# CR-10_Motherboard_2.net
KiCad netlist of a schematic drawn in Altium Designer
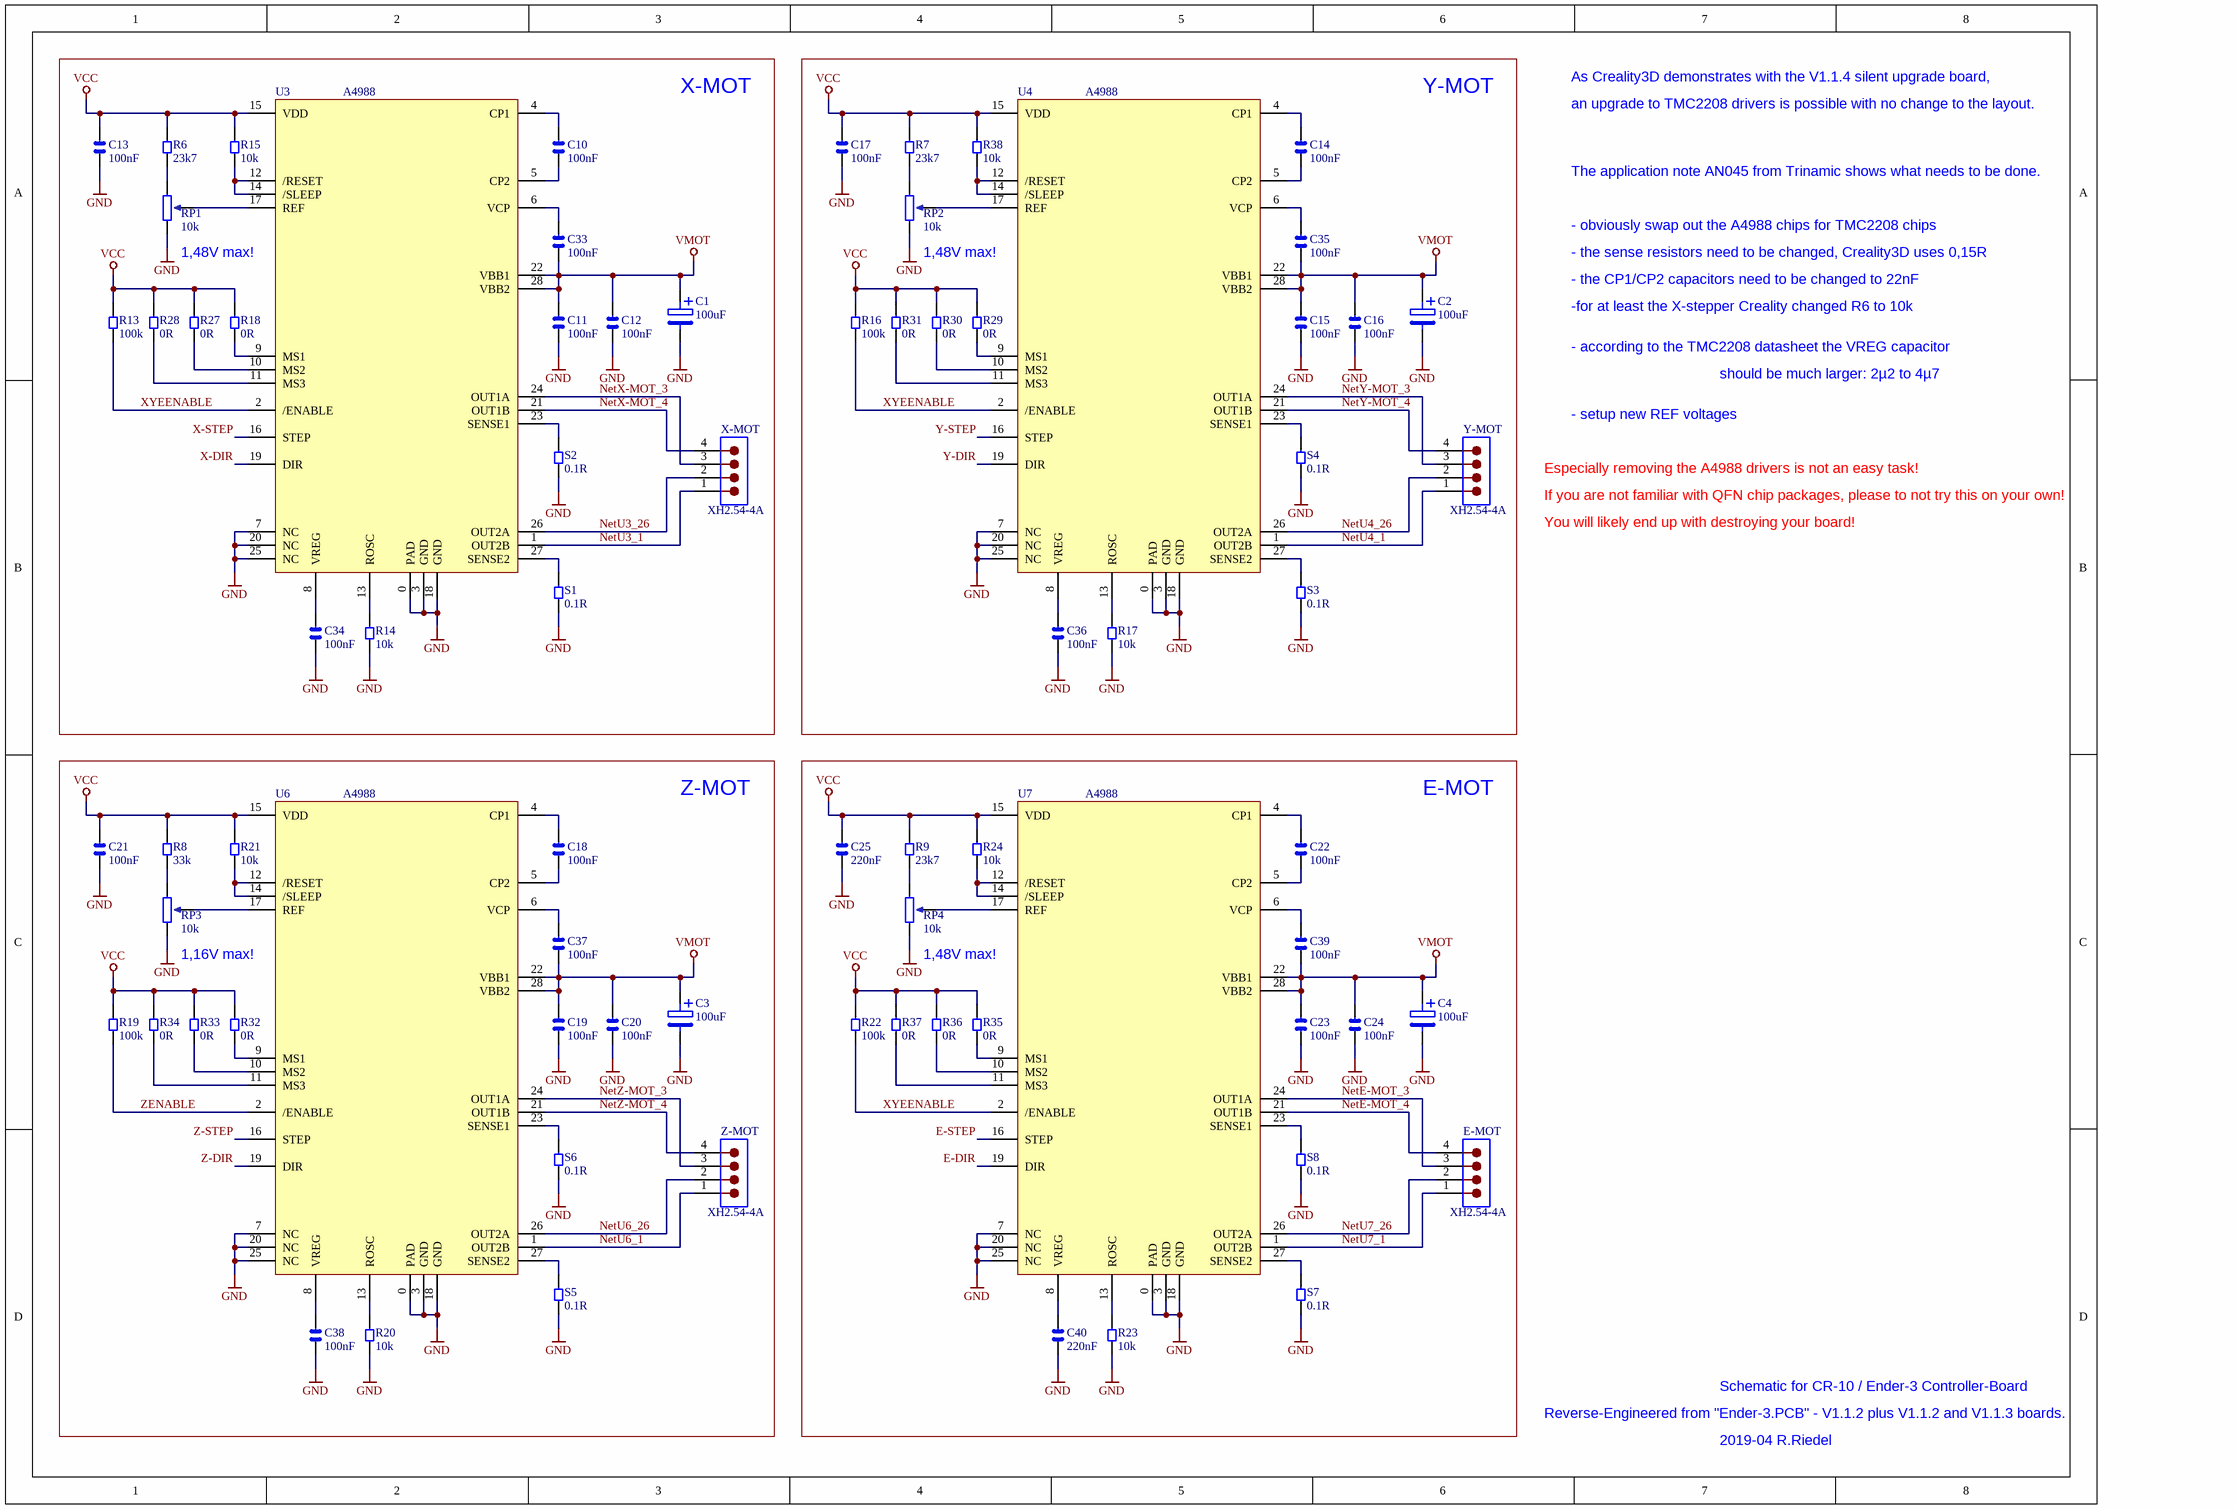
[diagram p0: CR-10 Motherboard_2.SchDoc]

(export (version "E")
  (design (tool "Eeschema 10.0.6"))
  (components
    (comp (ref "C1")
      (value "100uF")
      (footprint "Ender3:CAP-100")
      (description "Capacitor Polarized")
      (libsource (lib "CR-10 Motherboard") (part "Capacitor Pol"))
    )
    (comp (ref "C2")
      (value "100uF")
      (footprint "Ender3:CAP-100")
      (description "Capacitor Polarized")
      (libsource (lib "CR-10 Motherboard") (part "Capacitor Pol"))
    )
    (comp (ref "C3")
      (value "100uF")
      (footprint "Ender3:CAP-100")
      (description "Capacitor Polarized")
      (libsource (lib "CR-10 Motherboard") (part "Capacitor Pol"))
    )
    (comp (ref "C4")
      (value "100uF")
      (footprint "Ender3:CAP-100")
      (description "Capacitor Polarized")
      (libsource (lib "CR-10 Motherboard") (part "Capacitor Pol"))
    )
    (comp (ref "C10")
      (value "100nF")
      (footprint "Ender3:0603")
      (description "Chip Capacitor")
      (libsource (lib "CR-10 Motherboard") (part "Capacitor"))
    )
    (comp (ref "C11")
      (value "100nF")
      (footprint "Ender3:0603")
      (description "Chip Capacitor")
      (libsource (lib "CR-10 Motherboard") (part "Capacitor"))
    )
    (comp (ref "C12")
      (value "100nF")
      (footprint "Ender3:0603")
      (description "Chip Capacitor")
      (libsource (lib "CR-10 Motherboard") (part "Capacitor"))
    )
    (comp (ref "C13")
      (value "100nF")
      (footprint "Ender3:0603")
      (description "Chip Capacitor")
      (libsource (lib "CR-10 Motherboard") (part "Capacitor"))
    )
    (comp (ref "C14")
      (value "100nF")
      (footprint "Ender3:0603")
      (description "Chip Capacitor")
      (libsource (lib "CR-10 Motherboard") (part "Capacitor"))
    )
    (comp (ref "C15")
      (value "100nF")
      (footprint "Ender3:0603")
      (description "Chip Capacitor")
      (libsource (lib "CR-10 Motherboard") (part "Capacitor"))
    )
    (comp (ref "C16")
      (value "100nF")
      (footprint "Ender3:0603")
      (description "Chip Capacitor")
      (libsource (lib "CR-10 Motherboard") (part "Capacitor"))
    )
    (comp (ref "C17")
      (value "100nF")
      (footprint "Ender3:0603")
      (description "Chip Capacitor")
      (libsource (lib "CR-10 Motherboard") (part "Capacitor"))
    )
    (comp (ref "C18")
      (value "100nF")
      (footprint "Ender3:0603")
      (description "Chip Capacitor")
      (libsource (lib "CR-10 Motherboard") (part "Capacitor"))
    )
    (comp (ref "C19")
      (value "100nF")
      (footprint "Ender3:0603")
      (description "Chip Capacitor")
      (libsource (lib "CR-10 Motherboard") (part "Capacitor"))
    )
    (comp (ref "C20")
      (value "100nF")
      (footprint "Ender3:0603")
      (description "Chip Capacitor")
      (libsource (lib "CR-10 Motherboard") (part "Capacitor"))
    )
    (comp (ref "C21")
      (value "100nF")
      (footprint "Ender3:0603")
      (description "Chip Capacitor")
      (libsource (lib "CR-10 Motherboard") (part "Capacitor"))
    )
    (comp (ref "C22")
      (value "100nF")
      (footprint "Ender3:0603")
      (description "Chip Capacitor")
      (libsource (lib "CR-10 Motherboard") (part "Capacitor"))
    )
    (comp (ref "C23")
      (value "100nF")
      (footprint "Ender3:0603")
      (description "Chip Capacitor")
      (libsource (lib "CR-10 Motherboard") (part "Capacitor"))
    )
    (comp (ref "C24")
      (value "100nF")
      (footprint "Ender3:0603")
      (description "Chip Capacitor")
      (libsource (lib "CR-10 Motherboard") (part "Capacitor"))
    )
    (comp (ref "C25")
      (value "220nF")
      (footprint "Ender3:0603")
      (description "Chip Capacitor")
      (libsource (lib "CR-10 Motherboard") (part "Capacitor"))
    )
    (comp (ref "C33")
      (value "100nF")
      (footprint "Ender3:0603")
      (description "Chip Capacitor")
      (libsource (lib "CR-10 Motherboard") (part "Capacitor"))
    )
    (comp (ref "C34")
      (value "100nF")
      (footprint "Ender3:0603")
      (description "Chip Capacitor")
      (libsource (lib "CR-10 Motherboard") (part "Capacitor"))
    )
    (comp (ref "C35")
      (value "100nF")
      (footprint "Ender3:0603")
      (description "Chip Capacitor")
      (libsource (lib "CR-10 Motherboard") (part "Capacitor"))
    )
    (comp (ref "C36")
      (value "100nF")
      (footprint "Ender3:0603")
      (description "Chip Capacitor")
      (libsource (lib "CR-10 Motherboard") (part "Capacitor"))
    )
    (comp (ref "C37")
      (value "100nF")
      (footprint "Ender3:0603")
      (description "Chip Capacitor")
      (libsource (lib "CR-10 Motherboard") (part "Capacitor"))
    )
    (comp (ref "C38")
      (value "100nF")
      (footprint "Ender3:0603")
      (description "Chip Capacitor")
      (libsource (lib "CR-10 Motherboard") (part "Capacitor"))
    )
    (comp (ref "C39")
      (value "100nF")
      (footprint "Ender3:0603")
      (description "Chip Capacitor")
      (libsource (lib "CR-10 Motherboard") (part "Capacitor"))
    )
    (comp (ref "C40")
      (value "220nF")
      (footprint "Ender3:0603")
      (description "Chip Capacitor")
      (libsource (lib "CR-10 Motherboard") (part "Capacitor"))
    )
    (comp (ref "E-MOT")
      (value "XH2.54-4A")
      (footprint "Ender3:P4")
      (description "Header 1x4")
      (libsource (lib "CR-10 Motherboard") (part "Header 1x4"))
    )
    (comp (ref "R6")
      (value "23k7")
      (footprint "Ender3:0603")
      (description "Chip Resistor")
      (libsource (lib "CR-10 Motherboard") (part "Resistor"))
    )
    (comp (ref "R7")
      (value "23k7")
      (footprint "Ender3:0603")
      (description "Chip Resistor")
      (libsource (lib "CR-10 Motherboard") (part "Resistor"))
    )
    (comp (ref "R8")
      (value "33k")
      (footprint "Ender3:0603")
      (description "Chip Resistor")
      (libsource (lib "CR-10 Motherboard") (part "Resistor"))
    )
    (comp (ref "R9")
      (value "23k7")
      (footprint "Ender3:0603")
      (description "Chip Resistor")
      (libsource (lib "CR-10 Motherboard") (part "Resistor"))
    )
    (comp (ref "R13")
      (value "100k")
      (footprint "Ender3:0603")
      (description "Chip Resistor")
      (libsource (lib "CR-10 Motherboard") (part "Resistor"))
    )
    (comp (ref "R14")
      (value "10k")
      (footprint "Ender3:0603")
      (description "Chip Resistor")
      (libsource (lib "CR-10 Motherboard") (part "Resistor"))
    )
    (comp (ref "R15")
      (value "10k")
      (footprint "Ender3:0603")
      (description "Chip Resistor")
      (libsource (lib "CR-10 Motherboard") (part "Resistor"))
    )
    (comp (ref "R16")
      (value "100k")
      (footprint "Ender3:0603")
      (description "Chip Resistor")
      (libsource (lib "CR-10 Motherboard") (part "Resistor"))
    )
    (comp (ref "R17")
      (value "10k")
      (footprint "Ender3:0603")
      (description "Chip Resistor")
      (libsource (lib "CR-10 Motherboard") (part "Resistor"))
    )
    (comp (ref "R18")
      (value "0R")
      (footprint "Ender3:0603")
      (description "Chip Resistor")
      (libsource (lib "CR-10 Motherboard") (part "Resistor"))
    )
    (comp (ref "R19")
      (value "100k")
      (footprint "Ender3:0603")
      (description "Chip Resistor")
      (libsource (lib "CR-10 Motherboard") (part "Resistor"))
    )
    (comp (ref "R20")
      (value "10k")
      (footprint "Ender3:0603")
      (description "Chip Resistor")
      (libsource (lib "CR-10 Motherboard") (part "Resistor"))
    )
    (comp (ref "R21")
      (value "10k")
      (footprint "Ender3:0603")
      (description "Chip Resistor")
      (libsource (lib "CR-10 Motherboard") (part "Resistor"))
    )
    (comp (ref "R22")
      (value "100k")
      (footprint "Ender3:0603")
      (description "Chip Resistor")
      (libsource (lib "CR-10 Motherboard") (part "Resistor"))
    )
    (comp (ref "R23")
      (value "10k")
      (footprint "Ender3:0603")
      (description "Chip Resistor")
      (libsource (lib "CR-10 Motherboard") (part "Resistor"))
    )
    (comp (ref "R24")
      (value "10k")
      (footprint "Ender3:0603")
      (description "Chip Resistor")
      (libsource (lib "CR-10 Motherboard") (part "Resistor"))
    )
    (comp (ref "R27")
      (value "0R")
      (footprint "Ender3:0603")
      (description "Chip Resistor")
      (libsource (lib "CR-10 Motherboard") (part "Resistor"))
    )
    (comp (ref "R28")
      (value "0R")
      (footprint "Ender3:0603")
      (description "Chip Resistor")
      (libsource (lib "CR-10 Motherboard") (part "Resistor"))
    )
    (comp (ref "R29")
      (value "0R")
      (footprint "Ender3:0603")
      (description "Chip Resistor")
      (libsource (lib "CR-10 Motherboard") (part "Resistor"))
    )
    (comp (ref "R30")
      (value "0R")
      (footprint "Ender3:0603")
      (description "Chip Resistor")
      (libsource (lib "CR-10 Motherboard") (part "Resistor"))
    )
    (comp (ref "R31")
      (value "0R")
      (footprint "Ender3:0603")
      (description "Chip Resistor")
      (libsource (lib "CR-10 Motherboard") (part "Resistor"))
    )
    (comp (ref "R32")
      (value "0R")
      (footprint "Ender3:0603")
      (description "Chip Resistor")
      (libsource (lib "CR-10 Motherboard") (part "Resistor"))
    )
    (comp (ref "R33")
      (value "0R")
      (footprint "Ender3:0603")
      (description "Chip Resistor")
      (libsource (lib "CR-10 Motherboard") (part "Resistor"))
    )
    (comp (ref "R34")
      (value "0R")
      (footprint "Ender3:0603")
      (description "Chip Resistor")
      (libsource (lib "CR-10 Motherboard") (part "Resistor"))
    )
    (comp (ref "R35")
      (value "0R")
      (footprint "Ender3:0603")
      (description "Chip Resistor")
      (libsource (lib "CR-10 Motherboard") (part "Resistor"))
    )
    (comp (ref "R36")
      (value "0R")
      (footprint "Ender3:0603")
      (description "Chip Resistor")
      (libsource (lib "CR-10 Motherboard") (part "Resistor"))
    )
    (comp (ref "R37")
      (value "0R")
      (footprint "Ender3:0603")
      (description "Chip Resistor")
      (libsource (lib "CR-10 Motherboard") (part "Resistor"))
    )
    (comp (ref "R38")
      (value "10k")
      (footprint "Ender3:0603")
      (description "Chip Resistor")
      (libsource (lib "CR-10 Motherboard") (part "Resistor"))
    )
    (comp (ref "RP1")
      (value "10k")
      (footprint "Ender3:RP")
      (description "RTrimm")
      (libsource (lib "CR-10 Motherboard") (part "RTrimm"))
    )
    (comp (ref "RP2")
      (value "10k")
      (footprint "Ender3:RP")
      (description "RTrimm")
      (libsource (lib "CR-10 Motherboard") (part "RTrimm"))
    )
    (comp (ref "RP3")
      (value "10k")
      (footprint "Ender3:RP")
      (description "RTrimm")
      (libsource (lib "CR-10 Motherboard") (part "RTrimm"))
    )
    (comp (ref "RP4")
      (value "10k")
      (footprint "Ender3:RP")
      (description "RTrimm")
      (libsource (lib "CR-10 Motherboard") (part "RTrimm"))
    )
    (comp (ref "S1")
      (value "0.1R")
      (footprint "Ender3:R100")
      (description "Chip Resistor")
      (libsource (lib "CR-10 Motherboard") (part "Resistor"))
    )
    (comp (ref "S2")
      (value "0.1R")
      (footprint "Ender3:R100")
      (description "Chip Resistor")
      (libsource (lib "CR-10 Motherboard") (part "Resistor"))
    )
    (comp (ref "S3")
      (value "0.1R")
      (footprint "Ender3:R100")
      (description "Chip Resistor")
      (libsource (lib "CR-10 Motherboard") (part "Resistor"))
    )
    (comp (ref "S4")
      (value "0.1R")
      (footprint "Ender3:R100")
      (description "Chip Resistor")
      (libsource (lib "CR-10 Motherboard") (part "Resistor"))
    )
    (comp (ref "S5")
      (value "0.1R")
      (footprint "Ender3:R100")
      (description "Chip Resistor")
      (libsource (lib "CR-10 Motherboard") (part "Resistor"))
    )
    (comp (ref "S6")
      (value "0.1R")
      (footprint "Ender3:R100")
      (description "Chip Resistor")
      (libsource (lib "CR-10 Motherboard") (part "Resistor"))
    )
    (comp (ref "S7")
      (value "0.1R")
      (footprint "Ender3:R100")
      (description "Chip Resistor")
      (libsource (lib "CR-10 Motherboard") (part "Resistor"))
    )
    (comp (ref "S8")
      (value "0.1R")
      (footprint "Ender3:R100")
      (description "Chip Resistor")
      (libsource (lib "CR-10 Motherboard") (part "Resistor"))
    )
    (comp (ref "U3")
      (value "A4988")
      (footprint "Ender3:QFP28")
      (libsource (lib "CR-10 Motherboard") (part "A4988"))
    )
    (comp (ref "U4")
      (value "A4988")
      (footprint "Ender3:QFP28")
      (libsource (lib "CR-10 Motherboard") (part "A4988"))
    )
    (comp (ref "U6")
      (value "A4988")
      (footprint "Ender3:QFP28")
      (libsource (lib "CR-10 Motherboard") (part "A4988"))
    )
    (comp (ref "U7")
      (value "A4988")
      (footprint "Ender3:QFP28")
      (libsource (lib "CR-10 Motherboard") (part "A4988"))
    )
    (comp (ref "X-MOT")
      (value "XH2.54-4A")
      (footprint "Ender3:P4")
      (description "Header 1x4")
      (libsource (lib "CR-10 Motherboard") (part "Header 1x4"))
    )
    (comp (ref "Y-MOT")
      (value "XH2.54-4A")
      (footprint "Ender3:P4")
      (description "Header 1x4")
      (libsource (lib "CR-10 Motherboard") (part "Header 1x4"))
    )
    (comp (ref "Z-MOT")
      (value "XH2.54-4A")
      (footprint "Ender3:P4")
      (description "Header 1x4")
      (libsource (lib "CR-10 Motherboard") (part "Header 1x4"))
    )
  )
  (nets
    (net (code "1") (name "/E-DIR") (class "Default")
      (node (ref "U7") (pin "19") (pinfunction "DIR_19") (pintype "passive"))
    )
    (net (code "2") (name "/E-STEP") (class "Default")
      (node (ref "U7") (pin "16") (pinfunction "STEP_16") (pintype "passive"))
    )
    (net (code "3") (name "/NetE-MOT_3") (class "Default")
      (node (ref "E-MOT") (pin "3") (pinfunction "3_3") (pintype "passive"))
      (node (ref "U7") (pin "24") (pinfunction "OUT1A_24") (pintype "passive"))
    )
    (net (code "4") (name "/NetE-MOT_4") (class "Default")
      (node (ref "E-MOT") (pin "4") (pinfunction "4_4") (pintype "passive"))
      (node (ref "U7") (pin "21") (pinfunction "OUT1B_21") (pintype "passive"))
    )
    (net (code "5") (name "/NetU3_1") (class "Default")
      (node (ref "U3") (pin "1") (pinfunction "OUT2B_1") (pintype "passive"))
      (node (ref "X-MOT") (pin "1") (pinfunction "1_1") (pintype "passive"))
    )
    (net (code "6") (name "/NetU3_26") (class "Default")
      (node (ref "U3") (pin "26") (pinfunction "OUT2A_26") (pintype "passive"))
      (node (ref "X-MOT") (pin "2") (pinfunction "2_2") (pintype "passive"))
    )
    (net (code "7") (name "/NetU4_1") (class "Default")
      (node (ref "U4") (pin "1") (pinfunction "OUT2B_1") (pintype "passive"))
      (node (ref "Y-MOT") (pin "1") (pinfunction "1_1") (pintype "passive"))
    )
    (net (code "8") (name "/NetU4_26") (class "Default")
      (node (ref "U4") (pin "26") (pinfunction "OUT2A_26") (pintype "passive"))
      (node (ref "Y-MOT") (pin "2") (pinfunction "2_2") (pintype "passive"))
    )
    (net (code "9") (name "/NetU6_1") (class "Default")
      (node (ref "U6") (pin "1") (pinfunction "OUT2B_1") (pintype "passive"))
      (node (ref "Z-MOT") (pin "1") (pinfunction "1_1") (pintype "passive"))
    )
    (net (code "10") (name "/NetU6_26") (class "Default")
      (node (ref "U6") (pin "26") (pinfunction "OUT2A_26") (pintype "passive"))
      (node (ref "Z-MOT") (pin "2") (pinfunction "2_2") (pintype "passive"))
    )
    (net (code "11") (name "/NetU7_1") (class "Default")
      (node (ref "E-MOT") (pin "1") (pinfunction "1_1") (pintype "passive"))
      (node (ref "U7") (pin "1") (pinfunction "OUT2B_1") (pintype "passive"))
    )
    (net (code "12") (name "/NetU7_26") (class "Default")
      (node (ref "E-MOT") (pin "2") (pinfunction "2_2") (pintype "passive"))
      (node (ref "U7") (pin "26") (pinfunction "OUT2A_26") (pintype "passive"))
    )
    (net (code "13") (name "/NetX-MOT_3") (class "Default")
      (node (ref "U3") (pin "24") (pinfunction "OUT1A_24") (pintype "passive"))
      (node (ref "X-MOT") (pin "3") (pinfunction "3_3") (pintype "passive"))
    )
    (net (code "14") (name "/NetX-MOT_4") (class "Default")
      (node (ref "U3") (pin "21") (pinfunction "OUT1B_21") (pintype "passive"))
      (node (ref "X-MOT") (pin "4") (pinfunction "4_4") (pintype "passive"))
    )
    (net (code "15") (name "/NetY-MOT_3") (class "Default")
      (node (ref "U4") (pin "24") (pinfunction "OUT1A_24") (pintype "passive"))
      (node (ref "Y-MOT") (pin "3") (pinfunction "3_3") (pintype "passive"))
    )
    (net (code "16") (name "/NetY-MOT_4") (class "Default")
      (node (ref "U4") (pin "21") (pinfunction "OUT1B_21") (pintype "passive"))
      (node (ref "Y-MOT") (pin "4") (pinfunction "4_4") (pintype "passive"))
    )
    (net (code "17") (name "/NetZ-MOT_3") (class "Default")
      (node (ref "U6") (pin "24") (pinfunction "OUT1A_24") (pintype "passive"))
      (node (ref "Z-MOT") (pin "3") (pinfunction "3_3") (pintype "passive"))
    )
    (net (code "18") (name "/NetZ-MOT_4") (class "Default")
      (node (ref "U6") (pin "21") (pinfunction "OUT1B_21") (pintype "passive"))
      (node (ref "Z-MOT") (pin "4") (pinfunction "4_4") (pintype "passive"))
    )
    (net (code "19") (name "/X-DIR") (class "Default")
      (node (ref "U3") (pin "19") (pinfunction "DIR_19") (pintype "passive"))
    )
    (net (code "20") (name "/X-STEP") (class "Default")
      (node (ref "U3") (pin "16") (pinfunction "STEP_16") (pintype "passive"))
    )
    (net (code "21") (name "/XYEENABLE") (class "Default")
      (node (ref "R13") (pin "1") (pinfunction "1_1") (pintype "passive"))
      (node (ref "R16") (pin "1") (pinfunction "1_1") (pintype "passive"))
      (node (ref "R22") (pin "1") (pinfunction "1_1") (pintype "passive"))
      (node (ref "U3") (pin "2") (pinfunction "/ENABLE_2") (pintype "passive"))
      (node (ref "U4") (pin "2") (pinfunction "/ENABLE_2") (pintype "passive"))
      (node (ref "U7") (pin "2") (pinfunction "/ENABLE_2") (pintype "passive"))
    )
    (net (code "22") (name "/Y-DIR") (class "Default")
      (node (ref "U4") (pin "19") (pinfunction "DIR_19") (pintype "passive"))
    )
    (net (code "23") (name "/Y-STEP") (class "Default")
      (node (ref "U4") (pin "16") (pinfunction "STEP_16") (pintype "passive"))
    )
    (net (code "24") (name "/Z-DIR") (class "Default")
      (node (ref "U6") (pin "19") (pinfunction "DIR_19") (pintype "passive"))
    )
    (net (code "25") (name "/Z-STEP") (class "Default")
      (node (ref "U6") (pin "16") (pinfunction "STEP_16") (pintype "passive"))
    )
    (net (code "26") (name "/ZENABLE") (class "Default")
      (node (ref "R19") (pin "1") (pinfunction "1_1") (pintype "passive"))
      (node (ref "U6") (pin "2") (pinfunction "/ENABLE_2") (pintype "passive"))
    )
    (net (code "27") (name "GND") (class "Default")
      (node (ref "C1") (pin "2") (pinfunction "2_2") (pintype "passive"))
      (node (ref "C11") (pin "1") (pinfunction "1_1") (pintype "passive"))
      (node (ref "C12") (pin "2") (pinfunction "2_2") (pintype "passive"))
      (node (ref "C13") (pin "2") (pinfunction "2_2") (pintype "passive"))
      (node (ref "C15") (pin "1") (pinfunction "1_1") (pintype "passive"))
      (node (ref "C16") (pin "2") (pinfunction "2_2") (pintype "passive"))
      (node (ref "C17") (pin "2") (pinfunction "2_2") (pintype "passive"))
      (node (ref "C19") (pin "1") (pinfunction "1_1") (pintype "passive"))
      (node (ref "C2") (pin "2") (pinfunction "2_2") (pintype "passive"))
      (node (ref "C20") (pin "2") (pinfunction "2_2") (pintype "passive"))
      (node (ref "C21") (pin "2") (pinfunction "2_2") (pintype "passive"))
      (node (ref "C23") (pin "1") (pinfunction "1_1") (pintype "passive"))
      (node (ref "C24") (pin "2") (pinfunction "2_2") (pintype "passive"))
      (node (ref "C25") (pin "2") (pinfunction "2_2") (pintype "passive"))
      (node (ref "C3") (pin "2") (pinfunction "2_2") (pintype "passive"))
      (node (ref "C34") (pin "2") (pinfunction "2_2") (pintype "passive"))
      (node (ref "C36") (pin "2") (pinfunction "2_2") (pintype "passive"))
      (node (ref "C38") (pin "2") (pinfunction "2_2") (pintype "passive"))
      (node (ref "C4") (pin "2") (pinfunction "2_2") (pintype "passive"))
      (node (ref "C40") (pin "2") (pinfunction "2_2") (pintype "passive"))
      (node (ref "R14") (pin "2") (pinfunction "2_2") (pintype "passive"))
      (node (ref "R17") (pin "2") (pinfunction "2_2") (pintype "passive"))
      (node (ref "R20") (pin "2") (pinfunction "2_2") (pintype "passive"))
      (node (ref "R23") (pin "2") (pinfunction "2_2") (pintype "passive"))
      (node (ref "RP1") (pin "2") (pinfunction "2_2") (pintype "passive"))
      (node (ref "RP2") (pin "2") (pinfunction "2_2") (pintype "passive"))
      (node (ref "RP3") (pin "2") (pinfunction "2_2") (pintype "passive"))
      (node (ref "RP4") (pin "2") (pinfunction "2_2") (pintype "passive"))
      (node (ref "S1") (pin "2") (pinfunction "2_2") (pintype "passive"))
      (node (ref "S2") (pin "2") (pinfunction "2_2") (pintype "passive"))
      (node (ref "S3") (pin "2") (pinfunction "2_2") (pintype "passive"))
      (node (ref "S4") (pin "2") (pinfunction "2_2") (pintype "passive"))
      (node (ref "S5") (pin "2") (pinfunction "2_2") (pintype "passive"))
      (node (ref "S6") (pin "2") (pinfunction "2_2") (pintype "passive"))
      (node (ref "S7") (pin "2") (pinfunction "2_2") (pintype "passive"))
      (node (ref "S8") (pin "2") (pinfunction "2_2") (pintype "passive"))
      (node (ref "U3") (pin "0") (pinfunction "PAD_0") (pintype "passive"))
      (node (ref "U3") (pin "18") (pinfunction "GND_18") (pintype "passive"))
      (node (ref "U3") (pin "20") (pinfunction "NC_20") (pintype "passive"))
      (node (ref "U3") (pin "25") (pinfunction "NC_25") (pintype "passive"))
      (node (ref "U3") (pin "3") (pinfunction "GND_3") (pintype "passive"))
      (node (ref "U3") (pin "7") (pinfunction "NC_7") (pintype "passive"))
      (node (ref "U4") (pin "0") (pinfunction "PAD_0") (pintype "passive"))
      (node (ref "U4") (pin "18") (pinfunction "GND_18") (pintype "passive"))
      (node (ref "U4") (pin "20") (pinfunction "NC_20") (pintype "passive"))
      (node (ref "U4") (pin "25") (pinfunction "NC_25") (pintype "passive"))
      (node (ref "U4") (pin "3") (pinfunction "GND_3") (pintype "passive"))
      (node (ref "U4") (pin "7") (pinfunction "NC_7") (pintype "passive"))
      (node (ref "U6") (pin "0") (pinfunction "PAD_0") (pintype "passive"))
      (node (ref "U6") (pin "18") (pinfunction "GND_18") (pintype "passive"))
      (node (ref "U6") (pin "20") (pinfunction "NC_20") (pintype "passive"))
      (node (ref "U6") (pin "25") (pinfunction "NC_25") (pintype "passive"))
      (node (ref "U6") (pin "3") (pinfunction "GND_3") (pintype "passive"))
      (node (ref "U6") (pin "7") (pinfunction "NC_7") (pintype "passive"))
      (node (ref "U7") (pin "0") (pinfunction "PAD_0") (pintype "passive"))
      (node (ref "U7") (pin "18") (pinfunction "GND_18") (pintype "passive"))
      (node (ref "U7") (pin "20") (pinfunction "NC_20") (pintype "passive"))
      (node (ref "U7") (pin "25") (pinfunction "NC_25") (pintype "passive"))
      (node (ref "U7") (pin "3") (pinfunction "GND_3") (pintype "passive"))
      (node (ref "U7") (pin "7") (pinfunction "NC_7") (pintype "passive"))
    )
    (net (code "28") (name "Net-(R6-Pad1)") (class "Default")
      (node (ref "R6") (pin "1") (pinfunction "1_1") (pintype "passive"))
      (node (ref "RP1") (pin "3") (pinfunction "3_3") (pintype "passive"))
    )
    (net (code "29") (name "Net-(R7-Pad1)") (class "Default")
      (node (ref "R7") (pin "1") (pinfunction "1_1") (pintype "passive"))
      (node (ref "RP2") (pin "3") (pinfunction "3_3") (pintype "passive"))
    )
    (net (code "30") (name "Net-(R8-Pad1)") (class "Default")
      (node (ref "R8") (pin "1") (pinfunction "1_1") (pintype "passive"))
      (node (ref "RP3") (pin "3") (pinfunction "3_3") (pintype "passive"))
    )
    (net (code "31") (name "Net-(R9-Pad1)") (class "Default")
      (node (ref "R9") (pin "1") (pinfunction "1_1") (pintype "passive"))
      (node (ref "RP4") (pin "3") (pinfunction "3_3") (pintype "passive"))
    )
    (net (code "32") (name "Net-(U3-CP1)") (class "Default")
      (node (ref "C10") (pin "1") (pinfunction "1_1") (pintype "passive"))
      (node (ref "U3") (pin "4") (pinfunction "CP1_4") (pintype "passive"))
    )
    (net (code "33") (name "Net-(U3-CP2)") (class "Default")
      (node (ref "C10") (pin "2") (pinfunction "2_2") (pintype "passive"))
      (node (ref "U3") (pin "5") (pinfunction "CP2_5") (pintype "passive"))
    )
    (net (code "34") (name "Net-(U3-MS1)") (class "Default")
      (node (ref "R18") (pin "1") (pinfunction "1_1") (pintype "passive"))
      (node (ref "U3") (pin "9") (pinfunction "MS1_9") (pintype "passive"))
    )
    (net (code "35") (name "Net-(U3-MS2)") (class "Default")
      (node (ref "R27") (pin "1") (pinfunction "1_1") (pintype "passive"))
      (node (ref "U3") (pin "10") (pinfunction "MS2_10") (pintype "passive"))
    )
    (net (code "36") (name "Net-(U3-MS3)") (class "Default")
      (node (ref "R28") (pin "1") (pinfunction "1_1") (pintype "passive"))
      (node (ref "U3") (pin "11") (pinfunction "MS3_11") (pintype "passive"))
    )
    (net (code "37") (name "Net-(U3-REF)") (class "Default")
      (node (ref "RP1") (pin "1") (pinfunction "1_1") (pintype "passive"))
      (node (ref "U3") (pin "17") (pinfunction "REF_17") (pintype "passive"))
    )
    (net (code "38") (name "Net-(U3-ROSC)") (class "Default")
      (node (ref "R14") (pin "1") (pinfunction "1_1") (pintype "passive"))
      (node (ref "U3") (pin "13") (pinfunction "ROSC_13") (pintype "passive"))
    )
    (net (code "39") (name "Net-(U3-SENSE1)") (class "Default")
      (node (ref "S2") (pin "1") (pinfunction "1_1") (pintype "passive"))
      (node (ref "U3") (pin "23") (pinfunction "SENSE1_23") (pintype "passive"))
    )
    (net (code "40") (name "Net-(U3-SENSE2)") (class "Default")
      (node (ref "S1") (pin "1") (pinfunction "1_1") (pintype "passive"))
      (node (ref "U3") (pin "27") (pinfunction "SENSE2_27") (pintype "passive"))
    )
    (net (code "41") (name "Net-(U3-VCP)") (class "Default")
      (node (ref "C33") (pin "1") (pinfunction "1_1") (pintype "passive"))
      (node (ref "U3") (pin "6") (pinfunction "VCP_6") (pintype "passive"))
    )
    (net (code "42") (name "Net-(U3-VREG)") (class "Default")
      (node (ref "C34") (pin "1") (pinfunction "1_1") (pintype "passive"))
      (node (ref "U3") (pin "8") (pinfunction "VREG_8") (pintype "passive"))
    )
    (net (code "43") (name "Net-(U3-{slash}RESET)") (class "Default")
      (node (ref "R15") (pin "1") (pinfunction "1_1") (pintype "passive"))
      (node (ref "U3") (pin "12") (pinfunction "/RESET_12") (pintype "passive"))
      (node (ref "U3") (pin "14") (pinfunction "/SLEEP_14") (pintype "passive"))
    )
    (net (code "44") (name "Net-(U4-CP1)") (class "Default")
      (node (ref "C14") (pin "1") (pinfunction "1_1") (pintype "passive"))
      (node (ref "U4") (pin "4") (pinfunction "CP1_4") (pintype "passive"))
    )
    (net (code "45") (name "Net-(U4-CP2)") (class "Default")
      (node (ref "C14") (pin "2") (pinfunction "2_2") (pintype "passive"))
      (node (ref "U4") (pin "5") (pinfunction "CP2_5") (pintype "passive"))
    )
    (net (code "46") (name "Net-(U4-MS1)") (class "Default")
      (node (ref "R29") (pin "1") (pinfunction "1_1") (pintype "passive"))
      (node (ref "U4") (pin "9") (pinfunction "MS1_9") (pintype "passive"))
    )
    (net (code "47") (name "Net-(U4-MS2)") (class "Default")
      (node (ref "R30") (pin "1") (pinfunction "1_1") (pintype "passive"))
      (node (ref "U4") (pin "10") (pinfunction "MS2_10") (pintype "passive"))
    )
    (net (code "48") (name "Net-(U4-MS3)") (class "Default")
      (node (ref "R31") (pin "1") (pinfunction "1_1") (pintype "passive"))
      (node (ref "U4") (pin "11") (pinfunction "MS3_11") (pintype "passive"))
    )
    (net (code "49") (name "Net-(U4-REF)") (class "Default")
      (node (ref "RP2") (pin "1") (pinfunction "1_1") (pintype "passive"))
      (node (ref "U4") (pin "17") (pinfunction "REF_17") (pintype "passive"))
    )
    (net (code "50") (name "Net-(U4-ROSC)") (class "Default")
      (node (ref "R17") (pin "1") (pinfunction "1_1") (pintype "passive"))
      (node (ref "U4") (pin "13") (pinfunction "ROSC_13") (pintype "passive"))
    )
    (net (code "51") (name "Net-(U4-SENSE1)") (class "Default")
      (node (ref "S4") (pin "1") (pinfunction "1_1") (pintype "passive"))
      (node (ref "U4") (pin "23") (pinfunction "SENSE1_23") (pintype "passive"))
    )
    (net (code "52") (name "Net-(U4-SENSE2)") (class "Default")
      (node (ref "S3") (pin "1") (pinfunction "1_1") (pintype "passive"))
      (node (ref "U4") (pin "27") (pinfunction "SENSE2_27") (pintype "passive"))
    )
    (net (code "53") (name "Net-(U4-VCP)") (class "Default")
      (node (ref "C35") (pin "1") (pinfunction "1_1") (pintype "passive"))
      (node (ref "U4") (pin "6") (pinfunction "VCP_6") (pintype "passive"))
    )
    (net (code "54") (name "Net-(U4-VREG)") (class "Default")
      (node (ref "C36") (pin "1") (pinfunction "1_1") (pintype "passive"))
      (node (ref "U4") (pin "8") (pinfunction "VREG_8") (pintype "passive"))
    )
    (net (code "55") (name "Net-(U4-{slash}RESET)") (class "Default")
      (node (ref "R38") (pin "1") (pinfunction "1_1") (pintype "passive"))
      (node (ref "U4") (pin "12") (pinfunction "/RESET_12") (pintype "passive"))
      (node (ref "U4") (pin "14") (pinfunction "/SLEEP_14") (pintype "passive"))
    )
    (net (code "56") (name "Net-(U6-CP1)") (class "Default")
      (node (ref "C18") (pin "1") (pinfunction "1_1") (pintype "passive"))
      (node (ref "U6") (pin "4") (pinfunction "CP1_4") (pintype "passive"))
    )
    (net (code "57") (name "Net-(U6-CP2)") (class "Default")
      (node (ref "C18") (pin "2") (pinfunction "2_2") (pintype "passive"))
      (node (ref "U6") (pin "5") (pinfunction "CP2_5") (pintype "passive"))
    )
    (net (code "58") (name "Net-(U6-MS1)") (class "Default")
      (node (ref "R32") (pin "1") (pinfunction "1_1") (pintype "passive"))
      (node (ref "U6") (pin "9") (pinfunction "MS1_9") (pintype "passive"))
    )
    (net (code "59") (name "Net-(U6-MS2)") (class "Default")
      (node (ref "R33") (pin "1") (pinfunction "1_1") (pintype "passive"))
      (node (ref "U6") (pin "10") (pinfunction "MS2_10") (pintype "passive"))
    )
    (net (code "60") (name "Net-(U6-MS3)") (class "Default")
      (node (ref "R34") (pin "1") (pinfunction "1_1") (pintype "passive"))
      (node (ref "U6") (pin "11") (pinfunction "MS3_11") (pintype "passive"))
    )
    (net (code "61") (name "Net-(U6-REF)") (class "Default")
      (node (ref "RP3") (pin "1") (pinfunction "1_1") (pintype "passive"))
      (node (ref "U6") (pin "17") (pinfunction "REF_17") (pintype "passive"))
    )
    (net (code "62") (name "Net-(U6-ROSC)") (class "Default")
      (node (ref "R20") (pin "1") (pinfunction "1_1") (pintype "passive"))
      (node (ref "U6") (pin "13") (pinfunction "ROSC_13") (pintype "passive"))
    )
    (net (code "63") (name "Net-(U6-SENSE1)") (class "Default")
      (node (ref "S6") (pin "1") (pinfunction "1_1") (pintype "passive"))
      (node (ref "U6") (pin "23") (pinfunction "SENSE1_23") (pintype "passive"))
    )
    (net (code "64") (name "Net-(U6-SENSE2)") (class "Default")
      (node (ref "S5") (pin "1") (pinfunction "1_1") (pintype "passive"))
      (node (ref "U6") (pin "27") (pinfunction "SENSE2_27") (pintype "passive"))
    )
    (net (code "65") (name "Net-(U6-VCP)") (class "Default")
      (node (ref "C37") (pin "1") (pinfunction "1_1") (pintype "passive"))
      (node (ref "U6") (pin "6") (pinfunction "VCP_6") (pintype "passive"))
    )
    (net (code "66") (name "Net-(U6-VREG)") (class "Default")
      (node (ref "C38") (pin "1") (pinfunction "1_1") (pintype "passive"))
      (node (ref "U6") (pin "8") (pinfunction "VREG_8") (pintype "passive"))
    )
    (net (code "67") (name "Net-(U6-{slash}RESET)") (class "Default")
      (node (ref "R21") (pin "1") (pinfunction "1_1") (pintype "passive"))
      (node (ref "U6") (pin "12") (pinfunction "/RESET_12") (pintype "passive"))
      (node (ref "U6") (pin "14") (pinfunction "/SLEEP_14") (pintype "passive"))
    )
    (net (code "68") (name "Net-(U7-CP1)") (class "Default")
      (node (ref "C22") (pin "1") (pinfunction "1_1") (pintype "passive"))
      (node (ref "U7") (pin "4") (pinfunction "CP1_4") (pintype "passive"))
    )
    (net (code "69") (name "Net-(U7-CP2)") (class "Default")
      (node (ref "C22") (pin "2") (pinfunction "2_2") (pintype "passive"))
      (node (ref "U7") (pin "5") (pinfunction "CP2_5") (pintype "passive"))
    )
    (net (code "70") (name "Net-(U7-MS1)") (class "Default")
      (node (ref "R35") (pin "1") (pinfunction "1_1") (pintype "passive"))
      (node (ref "U7") (pin "9") (pinfunction "MS1_9") (pintype "passive"))
    )
    (net (code "71") (name "Net-(U7-MS2)") (class "Default")
      (node (ref "R36") (pin "1") (pinfunction "1_1") (pintype "passive"))
      (node (ref "U7") (pin "10") (pinfunction "MS2_10") (pintype "passive"))
    )
    (net (code "72") (name "Net-(U7-MS3)") (class "Default")
      (node (ref "R37") (pin "1") (pinfunction "1_1") (pintype "passive"))
      (node (ref "U7") (pin "11") (pinfunction "MS3_11") (pintype "passive"))
    )
    (net (code "73") (name "Net-(U7-REF)") (class "Default")
      (node (ref "RP4") (pin "1") (pinfunction "1_1") (pintype "passive"))
      (node (ref "U7") (pin "17") (pinfunction "REF_17") (pintype "passive"))
    )
    (net (code "74") (name "Net-(U7-ROSC)") (class "Default")
      (node (ref "R23") (pin "1") (pinfunction "1_1") (pintype "passive"))
      (node (ref "U7") (pin "13") (pinfunction "ROSC_13") (pintype "passive"))
    )
    (net (code "75") (name "Net-(U7-SENSE1)") (class "Default")
      (node (ref "S8") (pin "1") (pinfunction "1_1") (pintype "passive"))
      (node (ref "U7") (pin "23") (pinfunction "SENSE1_23") (pintype "passive"))
    )
    (net (code "76") (name "Net-(U7-SENSE2)") (class "Default")
      (node (ref "S7") (pin "1") (pinfunction "1_1") (pintype "passive"))
      (node (ref "U7") (pin "27") (pinfunction "SENSE2_27") (pintype "passive"))
    )
    (net (code "77") (name "Net-(U7-VCP)") (class "Default")
      (node (ref "C39") (pin "1") (pinfunction "1_1") (pintype "passive"))
      (node (ref "U7") (pin "6") (pinfunction "VCP_6") (pintype "passive"))
    )
    (net (code "78") (name "Net-(U7-VREG)") (class "Default")
      (node (ref "C40") (pin "1") (pinfunction "1_1") (pintype "passive"))
      (node (ref "U7") (pin "8") (pinfunction "VREG_8") (pintype "passive"))
    )
    (net (code "79") (name "Net-(U7-{slash}RESET)") (class "Default")
      (node (ref "R24") (pin "1") (pinfunction "1_1") (pintype "passive"))
      (node (ref "U7") (pin "12") (pinfunction "/RESET_12") (pintype "passive"))
      (node (ref "U7") (pin "14") (pinfunction "/SLEEP_14") (pintype "passive"))
    )
    (net (code "80") (name "VCC") (class "Default")
      (node (ref "C13") (pin "1") (pinfunction "1_1") (pintype "passive"))
      (node (ref "C17") (pin "1") (pinfunction "1_1") (pintype "passive"))
      (node (ref "C21") (pin "1") (pinfunction "1_1") (pintype "passive"))
      (node (ref "C25") (pin "1") (pinfunction "1_1") (pintype "passive"))
      (node (ref "R13") (pin "2") (pinfunction "2_2") (pintype "passive"))
      (node (ref "R15") (pin "2") (pinfunction "2_2") (pintype "passive"))
      (node (ref "R16") (pin "2") (pinfunction "2_2") (pintype "passive"))
      (node (ref "R18") (pin "2") (pinfunction "2_2") (pintype "passive"))
      (node (ref "R19") (pin "2") (pinfunction "2_2") (pintype "passive"))
      (node (ref "R21") (pin "2") (pinfunction "2_2") (pintype "passive"))
      (node (ref "R22") (pin "2") (pinfunction "2_2") (pintype "passive"))
      (node (ref "R24") (pin "2") (pinfunction "2_2") (pintype "passive"))
      (node (ref "R27") (pin "2") (pinfunction "2_2") (pintype "passive"))
      (node (ref "R28") (pin "2") (pinfunction "2_2") (pintype "passive"))
      (node (ref "R29") (pin "2") (pinfunction "2_2") (pintype "passive"))
      (node (ref "R30") (pin "2") (pinfunction "2_2") (pintype "passive"))
      (node (ref "R31") (pin "2") (pinfunction "2_2") (pintype "passive"))
      (node (ref "R32") (pin "2") (pinfunction "2_2") (pintype "passive"))
      (node (ref "R33") (pin "2") (pinfunction "2_2") (pintype "passive"))
      (node (ref "R34") (pin "2") (pinfunction "2_2") (pintype "passive"))
      (node (ref "R35") (pin "2") (pinfunction "2_2") (pintype "passive"))
      (node (ref "R36") (pin "2") (pinfunction "2_2") (pintype "passive"))
      (node (ref "R37") (pin "2") (pinfunction "2_2") (pintype "passive"))
      (node (ref "R38") (pin "2") (pinfunction "2_2") (pintype "passive"))
      (node (ref "R6") (pin "2") (pinfunction "2_2") (pintype "passive"))
      (node (ref "R7") (pin "2") (pinfunction "2_2") (pintype "passive"))
      (node (ref "R8") (pin "2") (pinfunction "2_2") (pintype "passive"))
      (node (ref "R9") (pin "2") (pinfunction "2_2") (pintype "passive"))
      (node (ref "U3") (pin "15") (pinfunction "VDD_15") (pintype "passive"))
      (node (ref "U4") (pin "15") (pinfunction "VDD_15") (pintype "passive"))
      (node (ref "U6") (pin "15") (pinfunction "VDD_15") (pintype "passive"))
      (node (ref "U7") (pin "15") (pinfunction "VDD_15") (pintype "passive"))
    )
    (net (code "81") (name "VMOT") (class "Default")
      (node (ref "C1") (pin "1") (pinfunction "1_1") (pintype "passive"))
      (node (ref "C11") (pin "2") (pinfunction "2_2") (pintype "passive"))
      (node (ref "C12") (pin "1") (pinfunction "1_1") (pintype "passive"))
      (node (ref "C15") (pin "2") (pinfunction "2_2") (pintype "passive"))
      (node (ref "C16") (pin "1") (pinfunction "1_1") (pintype "passive"))
      (node (ref "C19") (pin "2") (pinfunction "2_2") (pintype "passive"))
      (node (ref "C2") (pin "1") (pinfunction "1_1") (pintype "passive"))
      (node (ref "C20") (pin "1") (pinfunction "1_1") (pintype "passive"))
      (node (ref "C23") (pin "2") (pinfunction "2_2") (pintype "passive"))
      (node (ref "C24") (pin "1") (pinfunction "1_1") (pintype "passive"))
      (node (ref "C3") (pin "1") (pinfunction "1_1") (pintype "passive"))
      (node (ref "C33") (pin "2") (pinfunction "2_2") (pintype "passive"))
      (node (ref "C35") (pin "2") (pinfunction "2_2") (pintype "passive"))
      (node (ref "C37") (pin "2") (pinfunction "2_2") (pintype "passive"))
      (node (ref "C39") (pin "2") (pinfunction "2_2") (pintype "passive"))
      (node (ref "C4") (pin "1") (pinfunction "1_1") (pintype "passive"))
      (node (ref "U3") (pin "22") (pinfunction "VBB1_22") (pintype "passive"))
      (node (ref "U3") (pin "28") (pinfunction "VBB2_28") (pintype "passive"))
      (node (ref "U4") (pin "22") (pinfunction "VBB1_22") (pintype "passive"))
      (node (ref "U4") (pin "28") (pinfunction "VBB2_28") (pintype "passive"))
      (node (ref "U6") (pin "22") (pinfunction "VBB1_22") (pintype "passive"))
      (node (ref "U6") (pin "28") (pinfunction "VBB2_28") (pintype "passive"))
      (node (ref "U7") (pin "22") (pinfunction "VBB1_22") (pintype "passive"))
      (node (ref "U7") (pin "28") (pinfunction "VBB2_28") (pintype "passive"))
    )
  )
)
